# digit_led_controler.net
KiCad netlist of a schematic drawn in EAGLE
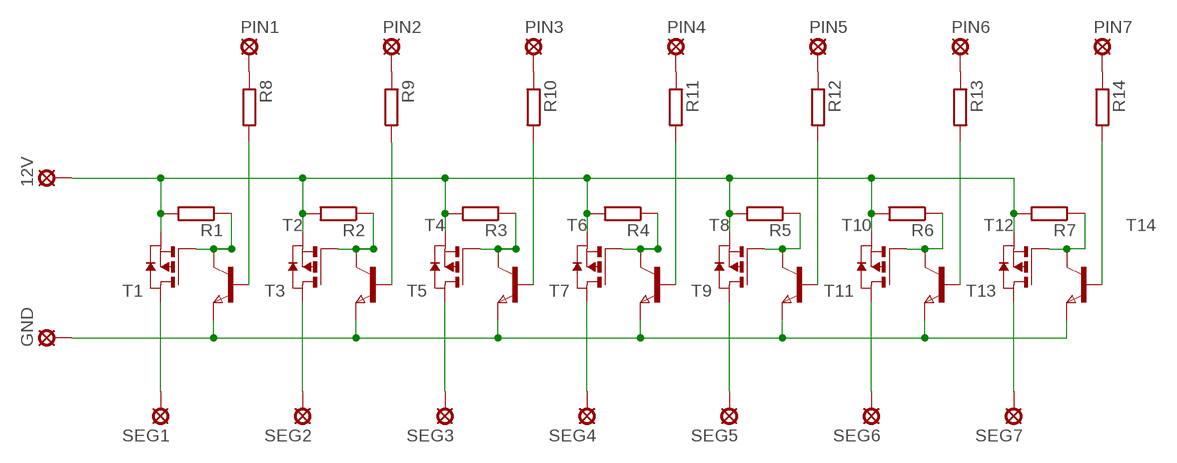
[diagram p0: schematic, sheet 1]

(export (version "E")
  (design (tool "Eeschema 10.0.6"))
  (components
    (comp (ref "12V")
      (value "SE14")
      (footprint "eagle-import:SE14")
      (libsource (lib "eagle-import") (part "SE14"))
    )
    (comp (ref "GND")
      (value "SE14")
      (footprint "eagle-import:SE14")
      (libsource (lib "eagle-import") (part "SE14"))
    )
    (comp (ref "PIN1")
      (value "SE14")
      (footprint "eagle-import:SE14")
      (libsource (lib "eagle-import") (part "SE14"))
    )
    (comp (ref "PIN2")
      (value "SE14")
      (footprint "eagle-import:SE14")
      (libsource (lib "eagle-import") (part "SE14"))
    )
    (comp (ref "PIN3")
      (value "SE14")
      (footprint "eagle-import:SE14")
      (libsource (lib "eagle-import") (part "SE14"))
    )
    (comp (ref "PIN4")
      (value "SE14")
      (footprint "eagle-import:SE14")
      (libsource (lib "eagle-import") (part "SE14"))
    )
    (comp (ref "PIN5")
      (value "SE14")
      (footprint "eagle-import:SE14")
      (libsource (lib "eagle-import") (part "SE14"))
    )
    (comp (ref "PIN6")
      (value "SE14")
      (footprint "eagle-import:SE14")
      (libsource (lib "eagle-import") (part "SE14"))
    )
    (comp (ref "PIN7")
      (value "SE14")
      (footprint "eagle-import:SE14")
      (libsource (lib "eagle-import") (part "SE14"))
    )
    (comp (ref "R1")
      (value "R-EU_R0805")
      (footprint "eagle-import:R0805")
      (libsource (lib "eagle-import") (part "R-EU_R0805"))
    )
    (comp (ref "R2")
      (value "R-EU_R0805")
      (footprint "eagle-import:R0805")
      (libsource (lib "eagle-import") (part "R-EU_R0805"))
    )
    (comp (ref "R3")
      (value "R-EU_R0805")
      (footprint "eagle-import:R0805")
      (libsource (lib "eagle-import") (part "R-EU_R0805"))
    )
    (comp (ref "R4")
      (value "R-EU_R0805")
      (footprint "eagle-import:R0805")
      (libsource (lib "eagle-import") (part "R-EU_R0805"))
    )
    (comp (ref "R5")
      (value "R-EU_R0805")
      (footprint "eagle-import:R0805")
      (libsource (lib "eagle-import") (part "R-EU_R0805"))
    )
    (comp (ref "R6")
      (value "R-EU_R0805")
      (footprint "eagle-import:R0805")
      (libsource (lib "eagle-import") (part "R-EU_R0805"))
    )
    (comp (ref "R7")
      (value "R-EU_R0805")
      (footprint "eagle-import:R0805")
      (libsource (lib "eagle-import") (part "R-EU_R0805"))
    )
    (comp (ref "R8")
      (value "R-EU_R0805")
      (footprint "eagle-import:R0805")
      (libsource (lib "eagle-import") (part "R-EU_R0805"))
    )
    (comp (ref "R9")
      (value "R-EU_R0805")
      (footprint "eagle-import:R0805")
      (libsource (lib "eagle-import") (part "R-EU_R0805"))
    )
    (comp (ref "R10")
      (value "R-EU_R0805")
      (footprint "eagle-import:R0805")
      (libsource (lib "eagle-import") (part "R-EU_R0805"))
    )
    (comp (ref "R11")
      (value "R-EU_R0805")
      (footprint "eagle-import:R0805")
      (libsource (lib "eagle-import") (part "R-EU_R0805"))
    )
    (comp (ref "R12")
      (value "R-EU_R0805")
      (footprint "eagle-import:R0805")
      (libsource (lib "eagle-import") (part "R-EU_R0805"))
    )
    (comp (ref "R13")
      (value "R-EU_R0805")
      (footprint "eagle-import:R0805")
      (libsource (lib "eagle-import") (part "R-EU_R0805"))
    )
    (comp (ref "R14")
      (value "R-EU_R0805")
      (footprint "eagle-import:R0805")
      (libsource (lib "eagle-import") (part "R-EU_R0805"))
    )
    (comp (ref "SEG1")
      (value "SE14")
      (footprint "eagle-import:SE14")
      (libsource (lib "eagle-import") (part "SE14"))
    )
    (comp (ref "SEG2")
      (value "SE14")
      (footprint "eagle-import:SE14")
      (libsource (lib "eagle-import") (part "SE14"))
    )
    (comp (ref "SEG3")
      (value "SE14")
      (footprint "eagle-import:SE14")
      (libsource (lib "eagle-import") (part "SE14"))
    )
    (comp (ref "SEG4")
      (value "SE14")
      (footprint "eagle-import:SE14")
      (libsource (lib "eagle-import") (part "SE14"))
    )
    (comp (ref "SEG5")
      (value "SE14")
      (footprint "eagle-import:SE14")
      (libsource (lib "eagle-import") (part "SE14"))
    )
    (comp (ref "SEG6")
      (value "SE14")
      (footprint "eagle-import:SE14")
      (libsource (lib "eagle-import") (part "SE14"))
    )
    (comp (ref "SEG7")
      (value "SE14")
      (footprint "eagle-import:SE14")
      (libsource (lib "eagle-import") (part "SE14"))
    )
    (comp (ref "T1")
      (value "PMOSSOT23")
      (footprint "eagle-import:SOT-23")
      (libsource (lib "eagle-import") (part "PMOSSOT23"))
    )
    (comp (ref "T2")
      (value "NPNSOT23")
      (footprint "eagle-import:SOT-23")
      (fields (field (name "MPN") "DSS20201L-7"))
      (libsource (lib "eagle-import") (part "NPNSOT23"))
    )
    (comp (ref "T3")
      (value "PMOSSOT23")
      (footprint "eagle-import:SOT-23")
      (libsource (lib "eagle-import") (part "PMOSSOT23"))
    )
    (comp (ref "T4")
      (value "NPNSOT23")
      (footprint "eagle-import:SOT-23")
      (fields (field (name "MPN") "DSS20201L-7"))
      (libsource (lib "eagle-import") (part "NPNSOT23"))
    )
    (comp (ref "T5")
      (value "PMOSSOT23")
      (footprint "eagle-import:SOT-23")
      (libsource (lib "eagle-import") (part "PMOSSOT23"))
    )
    (comp (ref "T6")
      (value "NPNSOT23")
      (footprint "eagle-import:SOT-23")
      (fields (field (name "MPN") "DSS20201L-7"))
      (libsource (lib "eagle-import") (part "NPNSOT23"))
    )
    (comp (ref "T7")
      (value "PMOSSOT23")
      (footprint "eagle-import:SOT-23")
      (libsource (lib "eagle-import") (part "PMOSSOT23"))
    )
    (comp (ref "T8")
      (value "NPNSOT23")
      (footprint "eagle-import:SOT-23")
      (fields (field (name "MPN") "DSS20201L-7"))
      (libsource (lib "eagle-import") (part "NPNSOT23"))
    )
    (comp (ref "T9")
      (value "PMOSSOT23")
      (footprint "eagle-import:SOT-23")
      (libsource (lib "eagle-import") (part "PMOSSOT23"))
    )
    (comp (ref "T10")
      (value "NPNSOT23")
      (footprint "eagle-import:SOT-23")
      (fields (field (name "MPN") "DSS20201L-7"))
      (libsource (lib "eagle-import") (part "NPNSOT23"))
    )
    (comp (ref "T11")
      (value "PMOSSOT23")
      (footprint "eagle-import:SOT-23")
      (libsource (lib "eagle-import") (part "PMOSSOT23"))
    )
    (comp (ref "T12")
      (value "NPNSOT23")
      (footprint "eagle-import:SOT-23")
      (fields (field (name "MPN") "DSS20201L-7"))
      (libsource (lib "eagle-import") (part "NPNSOT23"))
    )
    (comp (ref "T13")
      (value "PMOSSOT23")
      (footprint "eagle-import:SOT-23")
      (libsource (lib "eagle-import") (part "PMOSSOT23"))
    )
    (comp (ref "T14")
      (value "NPNSOT23")
      (footprint "eagle-import:SOT-23")
      (fields (field (name "MPN") "DSS20201L-7"))
      (libsource (lib "eagle-import") (part "NPNSOT23"))
    )
  )
  (nets
    (net (code "1") (name "Net-(PIN1-PadMP)") (class "Default")
      (node (ref "PIN1") (pin "MP") (pinfunction "MP_MP") (pintype "passive"))
      (node (ref "R8") (pin "1") (pinfunction "1_1") (pintype "passive"))
    )
    (net (code "2") (name "Net-(PIN2-PadMP)") (class "Default")
      (node (ref "PIN2") (pin "MP") (pinfunction "MP_MP") (pintype "passive"))
      (node (ref "R9") (pin "1") (pinfunction "1_1") (pintype "passive"))
    )
    (net (code "3") (name "Net-(PIN3-PadMP)") (class "Default")
      (node (ref "PIN3") (pin "MP") (pinfunction "MP_MP") (pintype "passive"))
      (node (ref "R10") (pin "1") (pinfunction "1_1") (pintype "passive"))
    )
    (net (code "4") (name "Net-(PIN4-PadMP)") (class "Default")
      (node (ref "PIN4") (pin "MP") (pinfunction "MP_MP") (pintype "passive"))
      (node (ref "R11") (pin "1") (pinfunction "1_1") (pintype "passive"))
    )
    (net (code "5") (name "Net-(PIN5-PadMP)") (class "Default")
      (node (ref "PIN5") (pin "MP") (pinfunction "MP_MP") (pintype "passive"))
      (node (ref "R12") (pin "1") (pinfunction "1_1") (pintype "passive"))
    )
    (net (code "6") (name "Net-(PIN6-PadMP)") (class "Default")
      (node (ref "PIN6") (pin "MP") (pinfunction "MP_MP") (pintype "passive"))
      (node (ref "R13") (pin "1") (pinfunction "1_1") (pintype "passive"))
    )
    (net (code "7") (name "Net-(PIN7-PadMP)") (class "Default")
      (node (ref "PIN7") (pin "MP") (pinfunction "MP_MP") (pintype "passive"))
      (node (ref "R14") (pin "1") (pinfunction "1_1") (pintype "passive"))
    )
    (net (code "8") (name "Net-(T1-D)") (class "Default")
      (node (ref "SEG1") (pin "MP") (pinfunction "MP_MP") (pintype "passive"))
      (node (ref "T1") (pin "1") (pinfunction "D_1") (pintype "passive"))
    )
    (net (code "9") (name "Net-(T1-G)") (class "Default")
      (node (ref "R1") (pin "1") (pinfunction "1_1") (pintype "passive"))
      (node (ref "T1") (pin "3") (pinfunction "G_3") (pintype "passive"))
      (node (ref "T2") (pin "1") (pinfunction "C_1") (pintype "passive"))
    )
    (net (code "10") (name "Net-(T1-S)") (class "Default")
      (node (ref "12V") (pin "MP") (pinfunction "MP_MP") (pintype "passive"))
      (node (ref "R1") (pin "2") (pinfunction "2_2") (pintype "passive"))
      (node (ref "R2") (pin "2") (pinfunction "2_2") (pintype "passive"))
      (node (ref "R3") (pin "2") (pinfunction "2_2") (pintype "passive"))
      (node (ref "R4") (pin "2") (pinfunction "2_2") (pintype "passive"))
      (node (ref "R5") (pin "2") (pinfunction "2_2") (pintype "passive"))
      (node (ref "R6") (pin "2") (pinfunction "2_2") (pintype "passive"))
      (node (ref "R7") (pin "2") (pinfunction "2_2") (pintype "passive"))
      (node (ref "T1") (pin "2") (pinfunction "S_2") (pintype "passive"))
      (node (ref "T11") (pin "2") (pinfunction "S_2") (pintype "passive"))
      (node (ref "T13") (pin "2") (pinfunction "S_2") (pintype "passive"))
      (node (ref "T3") (pin "2") (pinfunction "S_2") (pintype "passive"))
      (node (ref "T5") (pin "2") (pinfunction "S_2") (pintype "passive"))
      (node (ref "T7") (pin "2") (pinfunction "S_2") (pintype "passive"))
      (node (ref "T9") (pin "2") (pinfunction "S_2") (pintype "passive"))
    )
    (net (code "11") (name "Net-(T2-B)") (class "Default")
      (node (ref "R8") (pin "2") (pinfunction "2_2") (pintype "passive"))
      (node (ref "T2") (pin "3") (pinfunction "B_3") (pintype "passive"))
    )
    (net (code "12") (name "Net-(T3-D)") (class "Default")
      (node (ref "SEG2") (pin "MP") (pinfunction "MP_MP") (pintype "passive"))
      (node (ref "T3") (pin "1") (pinfunction "D_1") (pintype "passive"))
    )
    (net (code "13") (name "Net-(T3-G)") (class "Default")
      (node (ref "R2") (pin "1") (pinfunction "1_1") (pintype "passive"))
      (node (ref "T3") (pin "3") (pinfunction "G_3") (pintype "passive"))
      (node (ref "T4") (pin "1") (pinfunction "C_1") (pintype "passive"))
    )
    (net (code "14") (name "Net-(T4-B)") (class "Default")
      (node (ref "R9") (pin "2") (pinfunction "2_2") (pintype "passive"))
      (node (ref "T4") (pin "3") (pinfunction "B_3") (pintype "passive"))
    )
    (net (code "15") (name "Net-(T5-D)") (class "Default")
      (node (ref "SEG3") (pin "MP") (pinfunction "MP_MP") (pintype "passive"))
      (node (ref "T5") (pin "1") (pinfunction "D_1") (pintype "passive"))
    )
    (net (code "16") (name "Net-(T5-G)") (class "Default")
      (node (ref "R3") (pin "1") (pinfunction "1_1") (pintype "passive"))
      (node (ref "T5") (pin "3") (pinfunction "G_3") (pintype "passive"))
      (node (ref "T6") (pin "1") (pinfunction "C_1") (pintype "passive"))
    )
    (net (code "17") (name "Net-(T6-B)") (class "Default")
      (node (ref "R10") (pin "2") (pinfunction "2_2") (pintype "passive"))
      (node (ref "T6") (pin "3") (pinfunction "B_3") (pintype "passive"))
    )
    (net (code "18") (name "Net-(T7-D)") (class "Default")
      (node (ref "SEG4") (pin "MP") (pinfunction "MP_MP") (pintype "passive"))
      (node (ref "T7") (pin "1") (pinfunction "D_1") (pintype "passive"))
    )
    (net (code "19") (name "Net-(T7-G)") (class "Default")
      (node (ref "R4") (pin "1") (pinfunction "1_1") (pintype "passive"))
      (node (ref "T7") (pin "3") (pinfunction "G_3") (pintype "passive"))
      (node (ref "T8") (pin "1") (pinfunction "C_1") (pintype "passive"))
    )
    (net (code "20") (name "Net-(T8-B)") (class "Default")
      (node (ref "R11") (pin "2") (pinfunction "2_2") (pintype "passive"))
      (node (ref "T8") (pin "3") (pinfunction "B_3") (pintype "passive"))
    )
    (net (code "21") (name "Net-(T9-D)") (class "Default")
      (node (ref "SEG5") (pin "MP") (pinfunction "MP_MP") (pintype "passive"))
      (node (ref "T9") (pin "1") (pinfunction "D_1") (pintype "passive"))
    )
    (net (code "22") (name "Net-(T10-B)") (class "Default")
      (node (ref "R12") (pin "2") (pinfunction "2_2") (pintype "passive"))
      (node (ref "T10") (pin "3") (pinfunction "B_3") (pintype "passive"))
    )
    (net (code "23") (name "Net-(T10-C)") (class "Default")
      (node (ref "R5") (pin "1") (pinfunction "1_1") (pintype "passive"))
      (node (ref "T10") (pin "1") (pinfunction "C_1") (pintype "passive"))
      (node (ref "T9") (pin "3") (pinfunction "G_3") (pintype "passive"))
    )
    (net (code "24") (name "Net-(T10-E)") (class "Default")
      (node (ref "GND") (pin "MP") (pinfunction "MP_MP") (pintype "passive"))
      (node (ref "T10") (pin "2") (pinfunction "E_2") (pintype "passive"))
      (node (ref "T12") (pin "2") (pinfunction "E_2") (pintype "passive"))
      (node (ref "T14") (pin "2") (pinfunction "E_2") (pintype "passive"))
      (node (ref "T2") (pin "2") (pinfunction "E_2") (pintype "passive"))
      (node (ref "T4") (pin "2") (pinfunction "E_2") (pintype "passive"))
      (node (ref "T6") (pin "2") (pinfunction "E_2") (pintype "passive"))
      (node (ref "T8") (pin "2") (pinfunction "E_2") (pintype "passive"))
    )
    (net (code "25") (name "Net-(T11-D)") (class "Default")
      (node (ref "SEG6") (pin "MP") (pinfunction "MP_MP") (pintype "passive"))
      (node (ref "T11") (pin "1") (pinfunction "D_1") (pintype "passive"))
    )
    (net (code "26") (name "Net-(T11-G)") (class "Default")
      (node (ref "R6") (pin "1") (pinfunction "1_1") (pintype "passive"))
      (node (ref "T11") (pin "3") (pinfunction "G_3") (pintype "passive"))
      (node (ref "T12") (pin "1") (pinfunction "C_1") (pintype "passive"))
    )
    (net (code "27") (name "Net-(T12-B)") (class "Default")
      (node (ref "R13") (pin "2") (pinfunction "2_2") (pintype "passive"))
      (node (ref "T12") (pin "3") (pinfunction "B_3") (pintype "passive"))
    )
    (net (code "28") (name "Net-(T13-D)") (class "Default")
      (node (ref "SEG7") (pin "MP") (pinfunction "MP_MP") (pintype "passive"))
      (node (ref "T13") (pin "1") (pinfunction "D_1") (pintype "passive"))
    )
    (net (code "29") (name "Net-(T13-G)") (class "Default")
      (node (ref "R7") (pin "1") (pinfunction "1_1") (pintype "passive"))
      (node (ref "T13") (pin "3") (pinfunction "G_3") (pintype "passive"))
      (node (ref "T14") (pin "1") (pinfunction "C_1") (pintype "passive"))
    )
    (net (code "30") (name "Net-(T14-B)") (class "Default")
      (node (ref "R14") (pin "2") (pinfunction "2_2") (pintype "passive"))
      (node (ref "T14") (pin "3") (pinfunction "B_3") (pintype "passive"))
    )
  )
)
